# MCU.net
KiCad netlist of a schematic drawn in Altium Designer
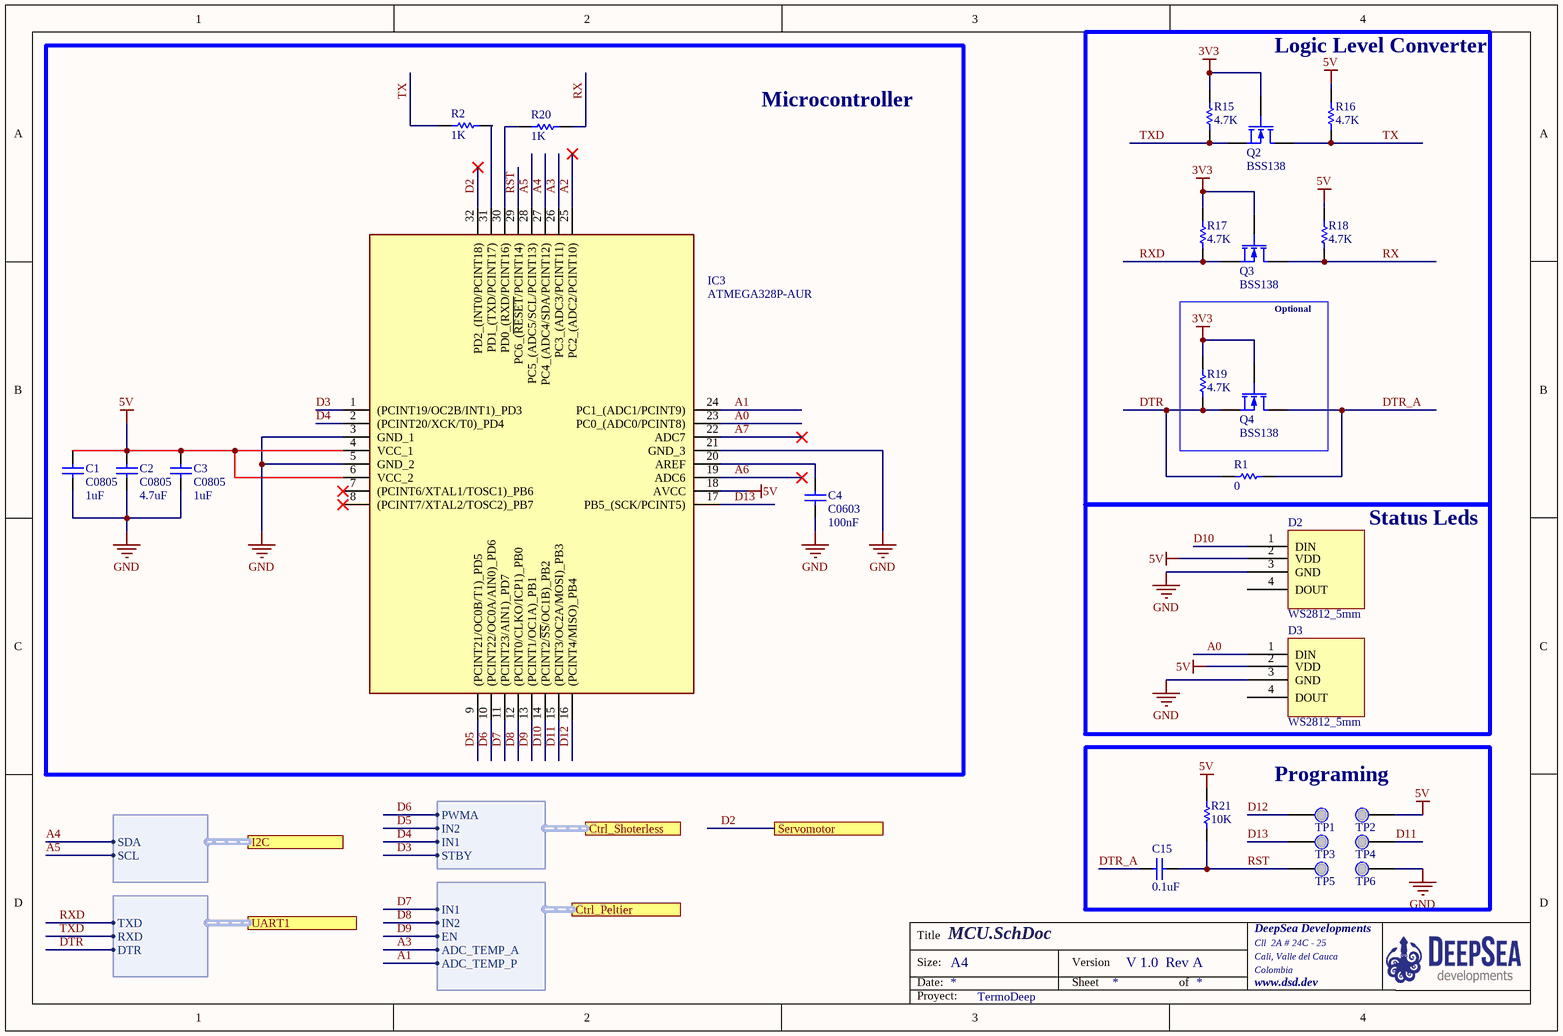
[diagram p0: MCU.SchDoc]

(export (version "E")
  (design (tool "Eeschema 10.0.6"))
  (components
    (comp (ref "C1")
      (value "C0805")
      (footprint "0805")
      (description "Ceramic Chip Capacitor - Standard")
      (fields (field (name "ALTIUM_VALUE") "1uF") (field (name "PUBLISHER") "Altium Limited"))
      (libsource (lib "KEMET Chip Capacitor") (part "C0805"))
    )
    (comp (ref "C2")
      (value "C0805")
      (footprint "0805")
      (description "Ceramic Chip Capacitor - Standard")
      (fields (field (name "ALTIUM_VALUE") "4.7uF") (field (name "PUBLISHER") "Altium Limited"))
      (libsource (lib "KEMET Chip Capacitor") (part "C0805"))
    )
    (comp (ref "C3")
      (value "C0805")
      (footprint "0805")
      (description "Ceramic Chip Capacitor - Standard")
      (fields (field (name "ALTIUM_VALUE") "1uF") (field (name "PUBLISHER") "Altium Limited"))
      (libsource (lib "KEMET Chip Capacitor") (part "C0805"))
    )
    (comp (ref "C4")
      (value "C0603")
      (footprint "CP0603_N")
      (description "Ceramic Chip Capacitor - Standard")
      (fields (field (name "ALTIUM_VALUE") "100nF") (field (name "PUBLISHER") "Altium Limited"))
      (libsource (lib "KEMET Chip Capacitor") (part "C0805"))
    )
    (comp (ref "C15") (value "0.1uF") (footprint "C0603_L") (libsource (lib "General") (part "C_SMD")))
    (comp (ref "D2")
      (value "WS2812_5mm")
      (footprint "Ws2812_5mm")
      (libsource (lib "SamacSys") (part "WS2812_5mm"))
    )
    (comp (ref "D3")
      (value "WS2812_5mm")
      (footprint "Ws2812_5mm")
      (libsource (lib "SamacSys") (part "WS2812_5mm"))
    )
    (comp (ref "IC3")
      (value "ATMEGA328P-AUR")
      (footprint "SamacSys:QFP80P900X900X120-32N")
      (description "Integrated Circuit")
      (fields
        (field (name "MANUFACTURER_PART_NUMBER") "ATMEGA328-AUR")
        (field (name "MOUSER PART NUMBER") "556-ATMEGA328-AUR")
      )
      (libsource (lib "*") (part "ATMEGA328-AUR"))
    )
    (comp (ref "Q2")
      (value "BSS138")
      (footprint "SOT23")
      (description "N-Channel Enhancement Mode Vertical DMOS FET")
      (fields (field (name "PUBLISHER") "Altium Limited"))
      (libsource (lib "IT PoolSys") (part "BSS138"))
    )
    (comp (ref "Q3")
      (value "BSS138")
      (footprint "SOT23")
      (description "N-Channel Enhancement Mode Vertical DMOS FET")
      (fields (field (name "PUBLISHER") "Altium Limited"))
      (libsource (lib "IT PoolSys") (part "BSS138"))
    )
    (comp (ref "Q4")
      (value "BSS138")
      (footprint "SOT23")
      (description "N-Channel Enhancement Mode Vertical DMOS FET")
      (fields (field (name "PUBLISHER") "Altium Limited"))
      (libsource (lib "IT PoolSys") (part "BSS138"))
    )
    (comp (ref "R1") (value "0") (footprint "footprints:R0603_N") (libsource (lib "General") (part "R_SMD")))
    (comp (ref "R2") (value "1K") (footprint "footprints:R0603_N") (libsource (lib "General") (part "R_SMD")))
    (comp (ref "R15")
      (value "4.7K")
      (footprint "footprints:R0603_N")
      (libsource (lib "General") (part "R_SMD"))
    )
    (comp (ref "R16")
      (value "4.7K")
      (footprint "footprints:R0603_N")
      (libsource (lib "General") (part "R_SMD"))
    )
    (comp (ref "R17")
      (value "4.7K")
      (footprint "footprints:R0603_N")
      (libsource (lib "General") (part "R_SMD"))
    )
    (comp (ref "R18")
      (value "4.7K")
      (footprint "footprints:R0603_N")
      (libsource (lib "General") (part "R_SMD"))
    )
    (comp (ref "R19")
      (value "4.7K")
      (footprint "footprints:R0603_N")
      (libsource (lib "General") (part "R_SMD"))
    )
    (comp (ref "R20")
      (value "1K")
      (footprint "footprints:R0603_N")
      (libsource (lib "General") (part "R_SMD"))
    )
    (comp (ref "R21")
      (value "10K")
      (footprint "footprints:R0603_N")
      (libsource (lib "General") (part "R_SMD"))
    )
    (comp (ref "TP1")
      (value "Test_Point")
      (footprint "TestPoint")
      (libsource (lib "General") (part "Test_Point"))
    )
    (comp (ref "TP2")
      (value "Test_Point")
      (footprint "TestPoint")
      (libsource (lib "General") (part "Test_Point"))
    )
    (comp (ref "TP3")
      (value "Test_Point")
      (footprint "TestPoint")
      (libsource (lib "General") (part "Test_Point"))
    )
    (comp (ref "TP4")
      (value "Test_Point")
      (footprint "TestPoint")
      (libsource (lib "General") (part "Test_Point"))
    )
    (comp (ref "TP5")
      (value "Test_Point")
      (footprint "TestPoint")
      (libsource (lib "General") (part "Test_Point"))
    )
    (comp (ref "TP6")
      (value "Test_Point")
      (footprint "TestPoint")
      (libsource (lib "General") (part "Test_Point"))
    )
  )
  (nets
    (net (code "5") (name "/A0") (class "Default")
      (node (ref "D3") (pin "1") (pinfunction "DIN_1") (pintype "passive"))
      (node (ref "IC3") (pin "23") (pinfunction "PC0_(ADC0/PCINT8)_23") (pintype "passive"))
    )
    (net (code "6") (name "/A1") (class "Default")
      (node (ref "IC3") (pin "24") (pinfunction "PC1_(ADC1/PCINT9)_24") (pintype "passive"))
    )
    (net (code "7") (name "/A2") (class "Default")
      (node (ref "IC3") (pin "25") (pinfunction "PC2_(ADC2/PCINT10)_25") (pintype "passive+no_connect"))
    )
    (net (code "8") (name "/A3") (class "Default")
      (node (ref "IC3") (pin "26") (pinfunction "PC3_(ADC3/PCINT11)_26") (pintype "passive"))
    )
    (net (code "9") (name "/A4") (class "Default")
      (node (ref "IC3") (pin "27") (pinfunction "PC4_(ADC4/SDA/PCINT12)_27") (pintype "passive"))
    )
    (net (code "10") (name "/A5") (class "Default")
      (node (ref "IC3") (pin "28") (pinfunction "PC5_(ADC5/SCL/PCINT13)_28") (pintype "passive"))
    )
    (net (code "11") (name "/A6") (class "Default")
      (node (ref "IC3") (pin "19") (pinfunction "ADC6_19") (pintype "passive+no_connect"))
    )
    (net (code "12") (name "/A7") (class "Default")
      (node (ref "IC3") (pin "22") (pinfunction "ADC7_22") (pintype "passive+no_connect"))
    )
    (net (code "13") (name "/D2") (class "Default")
      (node (ref "IC3") (pin "32") (pinfunction "PD2_(INT0/PCINT18)_32") (pintype "passive"))
    )
    (net (code "14") (name "/D3") (class "Default")
      (node (ref "IC3") (pin "1") (pinfunction "(PCINT19/OC2B/INT1)_PD3_1") (pintype "passive"))
    )
    (net (code "15") (name "/D4") (class "Default")
      (node (ref "IC3") (pin "2") (pinfunction "(PCINT20/XCK/T0)_PD4_2") (pintype "passive"))
    )
    (net (code "16") (name "/D5") (class "Default")
      (node (ref "IC3") (pin "9") (pinfunction "(PCINT21/OC0B/T1)_PD5_9") (pintype "passive"))
    )
    (net (code "17") (name "/D6") (class "Default")
      (node (ref "IC3") (pin "10") (pinfunction "(PCINT22/OC0A/AIN0)_PD6_10") (pintype "passive"))
    )
    (net (code "18") (name "/D7") (class "Default")
      (node (ref "IC3") (pin "11") (pinfunction "(PCINT23/AIN1)_PD7_11") (pintype "passive"))
    )
    (net (code "19") (name "/D8") (class "Default")
      (node (ref "IC3") (pin "12") (pinfunction "(PCINT0/CLKO/ICP1)_PB0_12") (pintype "passive"))
    )
    (net (code "20") (name "/D9") (class "Default")
      (node (ref "IC3") (pin "13") (pinfunction "(PCINT1/OC1A)_PB1_13") (pintype "passive"))
    )
    (net (code "21") (name "/D10") (class "Default")
      (node (ref "D2") (pin "1") (pinfunction "DIN_1") (pintype "passive"))
      (node (ref "IC3") (pin "14") (pinfunction "(PCINT2/~{SS}/OC1B)_PB2_14") (pintype "passive"))
    )
    (net (code "22") (name "/D11") (class "Default")
      (node (ref "IC3") (pin "15") (pinfunction "(PCINT3/OC2A/MOSI)_PB3_15") (pintype "passive"))
      (node (ref "TP4") (pin "0") (pinfunction "TP_0") (pintype "passive"))
    )
    (net (code "23") (name "/D12") (class "Default")
      (node (ref "IC3") (pin "16") (pinfunction "(PCINT4/MISO)_PB4_16") (pintype "passive"))
      (node (ref "TP1") (pin "0") (pinfunction "TP_0") (pintype "passive"))
    )
    (net (code "24") (name "/D13") (class "Default")
      (node (ref "IC3") (pin "17") (pinfunction "PB5_(SCK/PCINT5)_17") (pintype "passive"))
      (node (ref "TP3") (pin "0") (pinfunction "TP_0") (pintype "passive"))
    )
    (net (code "25") (name "/DTR") (class "Default")
      (node (ref "Q4") (pin "2") (pinfunction "S_2") (pintype "passive"))
      (node (ref "R1") (pin "1") (pinfunction "1_1") (pintype "passive"))
      (node (ref "R19") (pin "2") (pinfunction "2_2") (pintype "passive"))
    )
    (net (code "26") (name "/DTR_A") (class "Default")
      (node (ref "C15") (pin "1") (pinfunction "1_1") (pintype "passive"))
      (node (ref "Q4") (pin "1") (pinfunction "D_1") (pintype "passive"))
      (node (ref "R1") (pin "2") (pinfunction "2_2") (pintype "passive"))
    )
    (net (code "27") (name "/RST") (class "Default")
      (node (ref "C15") (pin "2") (pinfunction "2_2") (pintype "passive"))
      (node (ref "IC3") (pin "29") (pinfunction "PC6_(~{RESET}/PCINT14)_29") (pintype "passive"))
      (node (ref "R21") (pin "2") (pinfunction "2_2") (pintype "passive"))
      (node (ref "TP5") (pin "0") (pinfunction "TP_0") (pintype "passive"))
    )
    (net (code "28") (name "/RX") (class "Default")
      (node (ref "Q3") (pin "1") (pinfunction "D_1") (pintype "passive"))
      (node (ref "R18") (pin "2") (pinfunction "2_2") (pintype "passive"))
      (node (ref "R20") (pin "2") (pinfunction "2_2") (pintype "passive"))
    )
    (net (code "29") (name "/RXD") (class "Default")
      (node (ref "Q3") (pin "2") (pinfunction "S_2") (pintype "passive"))
      (node (ref "R17") (pin "2") (pinfunction "2_2") (pintype "passive"))
    )
    (net (code "30") (name "/TX") (class "Default")
      (node (ref "Q2") (pin "1") (pinfunction "D_1") (pintype "passive"))
      (node (ref "R16") (pin "2") (pinfunction "2_2") (pintype "passive"))
      (node (ref "R2") (pin "1") (pinfunction "1_1") (pintype "passive"))
    )
    (net (code "31") (name "/TXD") (class "Default")
      (node (ref "Q2") (pin "2") (pinfunction "S_2") (pintype "passive"))
      (node (ref "R15") (pin "2") (pinfunction "2_2") (pintype "passive"))
    )
    (net (code "36") (name "3V3") (class "Default")
      (node (ref "Q2") (pin "3") (pinfunction "G_3") (pintype "passive"))
      (node (ref "Q3") (pin "3") (pinfunction "G_3") (pintype "passive"))
      (node (ref "Q4") (pin "3") (pinfunction "G_3") (pintype "passive"))
      (node (ref "R15") (pin "1") (pinfunction "1_1") (pintype "passive"))
      (node (ref "R17") (pin "1") (pinfunction "1_1") (pintype "passive"))
      (node (ref "R19") (pin "1") (pinfunction "1_1") (pintype "passive"))
    )
    (net (code "37") (name "5V") (class "Default")
      (node (ref "C1") (pin "2") (pinfunction "2_2") (pintype "passive"))
      (node (ref "C2") (pin "2") (pinfunction "2_2") (pintype "passive"))
      (node (ref "C3") (pin "2") (pinfunction "2_2") (pintype "passive"))
      (node (ref "D2") (pin "2") (pinfunction "VDD_2") (pintype "passive"))
      (node (ref "D3") (pin "2") (pinfunction "VDD_2") (pintype "passive"))
      (node (ref "IC3") (pin "18") (pinfunction "AVCC_18") (pintype "passive"))
      (node (ref "IC3") (pin "4") (pinfunction "VCC_1_4") (pintype "passive"))
      (node (ref "IC3") (pin "6") (pinfunction "VCC_2_6") (pintype "passive"))
      (node (ref "R16") (pin "1") (pinfunction "1_1") (pintype "passive"))
      (node (ref "R18") (pin "1") (pinfunction "1_1") (pintype "passive"))
      (node (ref "R21") (pin "1") (pinfunction "1_1") (pintype "passive"))
      (node (ref "TP2") (pin "0") (pinfunction "TP_0") (pintype "passive"))
    )
    (net (code "38") (name "GND") (class "Default")
      (node (ref "C1") (pin "1") (pinfunction "1_1") (pintype "passive"))
      (node (ref "C2") (pin "1") (pinfunction "1_1") (pintype "passive"))
      (node (ref "C3") (pin "1") (pinfunction "1_1") (pintype "passive"))
      (node (ref "C4") (pin "1") (pinfunction "1_1") (pintype "passive"))
      (node (ref "D2") (pin "3") (pinfunction "GND_3") (pintype "passive"))
      (node (ref "D3") (pin "3") (pinfunction "GND_3") (pintype "passive"))
      (node (ref "IC3") (pin "21") (pinfunction "GND_3_21") (pintype "passive"))
      (node (ref "IC3") (pin "3") (pinfunction "GND_1_3") (pintype "passive"))
      (node (ref "IC3") (pin "5") (pinfunction "GND_2_5") (pintype "passive"))
      (node (ref "TP6") (pin "0") (pinfunction "TP_0") (pintype "passive"))
    )
    (net (code "39") (name "Net-(IC3-AREF)") (class "Default")
      (node (ref "C4") (pin "2") (pinfunction "2_2") (pintype "passive"))
      (node (ref "IC3") (pin "20") (pinfunction "AREF_20") (pintype "passive"))
    )
    (net (code "40") (name "Net-(IC3-PD0_(RXD{slash}PCINT16))") (class "Default")
      (node (ref "IC3") (pin "30") (pinfunction "PD0_(RXD/PCINT16)_30") (pintype "passive"))
      (node (ref "R20") (pin "1") (pinfunction "1_1") (pintype "passive"))
    )
    (net (code "41") (name "Net-(IC3-PD1_(TXD{slash}PCINT17))") (class "Default")
      (node (ref "IC3") (pin "31") (pinfunction "PD1_(TXD/PCINT17)_31") (pintype "passive"))
      (node (ref "R2") (pin "2") (pinfunction "2_2") (pintype "passive"))
    )
    (net (code "42") (name "unconnected-(D2-DOUT-Pad4)") (class "Default")
      (node (ref "D2") (pin "4") (pinfunction "DOUT_4") (pintype "passive"))
    )
    (net (code "43") (name "unconnected-(D3-DOUT-Pad4)") (class "Default")
      (node (ref "D3") (pin "4") (pinfunction "DOUT_4") (pintype "passive"))
    )
    (net (code "44") (name "unconnected-(IC3-(PCINT6{slash}XTAL1{slash}TOSC1)_PB6-Pad7)") (class "Default")
      (node (ref "IC3") (pin "7") (pinfunction "(PCINT6/XTAL1/TOSC1)_PB6_7") (pintype "passive+no_connect"))
    )
    (net (code "45") (name "unconnected-(IC3-(PCINT7{slash}XTAL2{slash}TOSC2)_PB7-Pad8)") (class "Default")
      (node (ref "IC3") (pin "8") (pinfunction "(PCINT7/XTAL2/TOSC2)_PB7_8") (pintype "passive+no_connect"))
    )
  )
)
